# ESP12_RGBW_00.net
KiCad netlist of a schematic drawn in Altium Designer
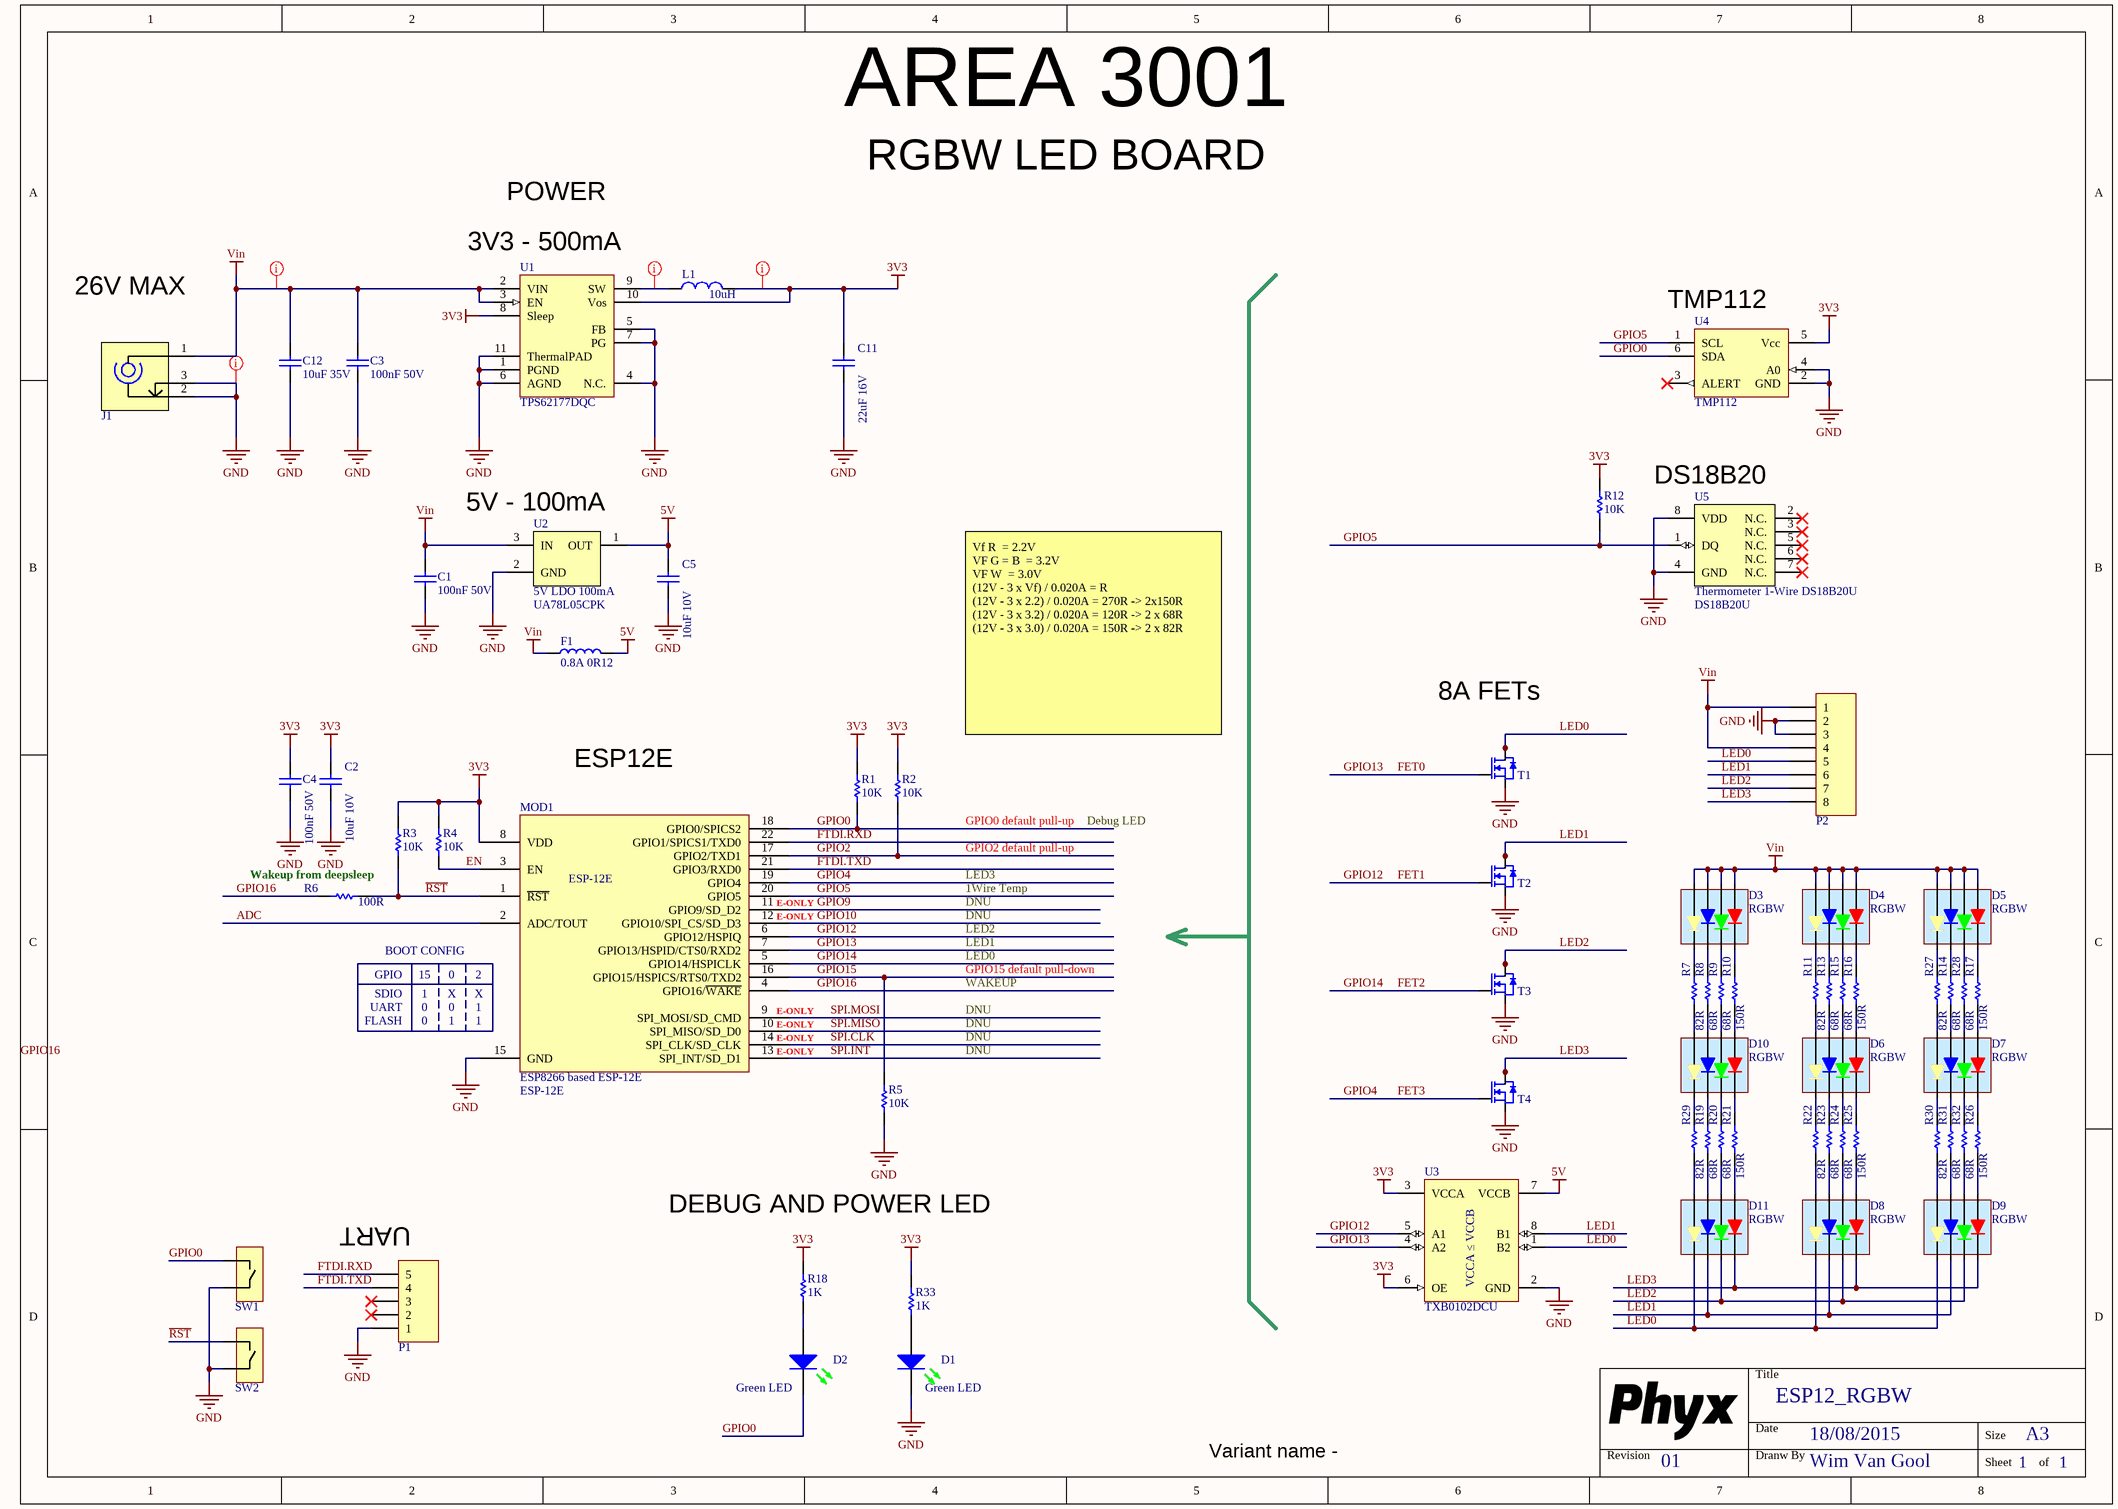
[diagram p0: ESP12_RGBW_00.SchDoc]

(export (version "E")
  (design (tool "Eeschema 10.0.6"))
  (components
    (comp (ref "C1")
      (value "100nF 50V")
      (footprint "C0603_N")
      (description "Capacitor Ceramic")
      (fields (field (name "Comment") "CAP_CERAMIC"))
      (libsource (lib "Phyx_Components") (part "CAP_CERAMIC"))
    )
    (comp (ref "C2")
      (value "10uF 10V")
      (footprint "C1206_N")
      (description "Capacitor Ceramic")
      (fields (field (name "Comment") "CAP_CERAMIC"))
      (libsource (lib "Phyx_Components") (part "CAP_CERAMIC"))
    )
    (comp (ref "C3")
      (value "100nF 50V")
      (footprint "C0603_N")
      (description "Capacitor Ceramic")
      (fields (field (name "Comment") "CAP_CERAMIC"))
      (libsource (lib "Phyx_Components") (part "CAP_CERAMIC"))
    )
    (comp (ref "C4")
      (value "100nF 50V")
      (footprint "C0603_N")
      (description "Capacitor Ceramic")
      (fields (field (name "Comment") "CAP_CERAMIC"))
      (libsource (lib "Phyx_Components") (part "CAP_CERAMIC"))
    )
    (comp (ref "C5")
      (value "10uF 10V")
      (footprint "C1206_N")
      (description "Capacitor Ceramic")
      (fields (field (name "Comment") "CAP_CERAMIC"))
      (libsource (lib "Phyx_Components") (part "CAP_CERAMIC"))
    )
    (comp (ref "C11")
      (value "22uF 16V")
      (footprint "C1206_N")
      (description "Capacitor Ceramic")
      (fields (field (name "Comment") "CAP_CERAMIC"))
      (libsource (lib "Phyx_Components") (part "CAP_CERAMIC"))
    )
    (comp (ref "C12")
      (value "10uF 35V")
      (footprint "C1206_N")
      (description "Capacitor Ceramic")
      (fields (field (name "Comment") "CAP_CERAMIC"))
      (libsource (lib "Phyx_Components") (part "CAP_CERAMIC"))
    )
    (comp (ref "D1")
      (value "Green LED")
      (footprint "LED_0805_GR")
      (description "=Description")
      (libsource (lib "Phyx_Components") (part "LED_GREEN"))
    )
    (comp (ref "D2")
      (value "Green LED")
      (footprint "LED_0805_GR")
      (description "=Description")
      (libsource (lib "Phyx_Components") (part "LED_GREEN"))
    )
    (comp (ref "D3")
      (value "RGBW")
      (footprint "LED_5050_RGBW_PLCC8")
      (description "=Description")
      (fields (field (name "Comment") "5050 RGBW LED"))
      (libsource (lib "Phyx_Components") (part "LED_RGBW"))
    )
    (comp (ref "D4")
      (value "RGBW")
      (footprint "LED_5050_RGBW_PLCC8")
      (description "=Description")
      (fields (field (name "Comment") "5050 RGBW LED"))
      (libsource (lib "Phyx_Components") (part "LED_RGBW"))
    )
    (comp (ref "D5")
      (value "RGBW")
      (footprint "LED_5050_RGBW_PLCC8")
      (description "=Description")
      (fields (field (name "Comment") "5050 RGBW LED"))
      (libsource (lib "Phyx_Components") (part "LED_RGBW"))
    )
    (comp (ref "D6")
      (value "RGBW")
      (footprint "LED_5050_RGBW_PLCC8")
      (description "=Description")
      (fields (field (name "Comment") "5050 RGBW LED"))
      (libsource (lib "Phyx_Components") (part "LED_RGBW"))
    )
    (comp (ref "D7")
      (value "RGBW")
      (footprint "LED_5050_RGBW_PLCC8")
      (description "=Description")
      (fields (field (name "Comment") "5050 RGBW LED"))
      (libsource (lib "Phyx_Components") (part "LED_RGBW"))
    )
    (comp (ref "D8")
      (value "RGBW")
      (footprint "LED_5050_RGBW_PLCC8")
      (description "=Description")
      (fields (field (name "Comment") "5050 RGBW LED"))
      (libsource (lib "Phyx_Components") (part "LED_RGBW"))
    )
    (comp (ref "D9")
      (value "RGBW")
      (footprint "LED_5050_RGBW_PLCC8")
      (description "=Description")
      (fields (field (name "Comment") "5050 RGBW LED"))
      (libsource (lib "Phyx_Components") (part "LED_RGBW"))
    )
    (comp (ref "D10")
      (value "RGBW")
      (footprint "LED_5050_RGBW_PLCC8")
      (description "=Description")
      (fields (field (name "Comment") "5050 RGBW LED"))
      (libsource (lib "Phyx_Components") (part "LED_RGBW"))
    )
    (comp (ref "D11")
      (value "RGBW")
      (footprint "LED_5050_RGBW_PLCC8")
      (description "=Description")
      (fields (field (name "Comment") "5050 RGBW LED"))
      (libsource (lib "Phyx_Components") (part "LED_RGBW"))
    )
    (comp (ref "F1")
      (value "0.8A 0R12")
      (footprint "L0805")
      (fields (field (name "Comment") "FERRITE"))
      (libsource (lib "Phyx_Components") (part "FERRITE"))
    )
    (comp (ref "J1")
      (value "Socket RA 4.75 with 1.75 barrel")
      (footprint "694105309102")
      (description "Socket RA 5.5  with 2.1 barrel")
      (libsource (lib "Phyx_Components") (part "Cliff_DC10"))
    )
    (comp (ref "L1")
      (value "10uH")
      (footprint "BRNS_SDR0503")
      (fields (field (name "Comment") "SDR0503-100ML"))
      (libsource (lib "Phyx_Components") (part "INDUCTOR"))
    )
    (comp (ref "MOD1")
      (value "ESP8266 based ESP-12E")
      (footprint "ESP-12E")
      (description "=Description")
      (fields (field (name "ALTIUM_VALUE") "ESP-12E"))
      (libsource (lib "Phyx_Components") (part "ESP-12E"))
    )
    (comp (ref "P1")
      (value "Header 5")
      (footprint "HDR1X5")
      (description "Pin Header 2.54mm 5way")
      (libsource (lib "Phyx_Components") (part "Header 5"))
    )
    (comp (ref "P2")
      (value "8 Terminal Socket RA 3,5mm")
      (footprint "WE_691322110008")
      (libsource (lib "Phyx_Components") (part "Header 8"))
    )
    (comp (ref "R1")
      (value "10K")
      (footprint "R0603_N")
      (fields (field (name "Comment") "RESISTOR"))
      (libsource (lib "Phyx_Components") (part "RESISTOR"))
    )
    (comp (ref "R2")
      (value "10K")
      (footprint "R0603_N")
      (fields (field (name "Comment") "RESISTOR"))
      (libsource (lib "Phyx_Components") (part "RESISTOR"))
    )
    (comp (ref "R3")
      (value "10K")
      (footprint "R0603_N")
      (fields (field (name "Comment") "RESISTOR"))
      (libsource (lib "Phyx_Components") (part "RESISTOR"))
    )
    (comp (ref "R4")
      (value "10K")
      (footprint "R0603_N")
      (fields (field (name "Comment") "RESISTOR"))
      (libsource (lib "Phyx_Components") (part "RESISTOR"))
    )
    (comp (ref "R5")
      (value "10K")
      (footprint "R0603_N")
      (fields (field (name "Comment") "RESISTOR"))
      (libsource (lib "Phyx_Components") (part "RESISTOR"))
    )
    (comp (ref "R6")
      (value "100R")
      (footprint "R0603_N")
      (fields (field (name "Comment") "RESISTOR"))
      (libsource (lib "Phyx_Components") (part "RESISTOR"))
    )
    (comp (ref "R7")
      (value "82R")
      (footprint "R0603_N")
      (description "RES # 82R 0603")
      (fields (field (name "Comment") "RESISTOR"))
      (libsource (lib "Phyx_Components") (part "RESISTOR"))
    )
    (comp (ref "R8")
      (value "68R")
      (footprint "R0603_N")
      (fields (field (name "Comment") "RESISTOR"))
      (libsource (lib "Phyx_Components") (part "RESISTOR"))
    )
    (comp (ref "R9")
      (value "68R")
      (footprint "R0603_N")
      (fields (field (name "Comment") "RESISTOR"))
      (libsource (lib "Phyx_Components") (part "RESISTOR"))
    )
    (comp (ref "R10")
      (value "150R")
      (footprint "R0603_N")
      (description "RES # 150R 0603")
      (fields (field (name "Comment") "RESISTOR"))
      (libsource (lib "Phyx_Components") (part "RESISTOR"))
    )
    (comp (ref "R11")
      (value "82R")
      (footprint "R0603_N")
      (description "RES # 82R 0603")
      (fields (field (name "Comment") "RESISTOR"))
      (libsource (lib "Phyx_Components") (part "RESISTOR"))
    )
    (comp (ref "R12")
      (value "10K")
      (footprint "R0603_N")
      (fields (field (name "Comment") "RESISTOR"))
      (libsource (lib "Phyx_Components") (part "RESISTOR"))
    )
    (comp (ref "R13")
      (value "68R")
      (footprint "R0603_N")
      (fields (field (name "Comment") "RESISTOR"))
      (libsource (lib "Phyx_Components") (part "RESISTOR"))
    )
    (comp (ref "R14")
      (value "68R")
      (footprint "R0603_N")
      (fields (field (name "Comment") "RESISTOR"))
      (libsource (lib "Phyx_Components") (part "RESISTOR"))
    )
    (comp (ref "R15")
      (value "68R")
      (footprint "R0603_N")
      (fields (field (name "Comment") "RESISTOR"))
      (libsource (lib "Phyx_Components") (part "RESISTOR"))
    )
    (comp (ref "R16")
      (value "150R")
      (footprint "R0603_N")
      (description "RES # 150R 0603")
      (fields (field (name "Comment") "RESISTOR"))
      (libsource (lib "Phyx_Components") (part "RESISTOR"))
    )
    (comp (ref "R17")
      (value "150R")
      (footprint "R0603_N")
      (description "RES # 150R 0603")
      (fields (field (name "Comment") "RESISTOR"))
      (libsource (lib "Phyx_Components") (part "RESISTOR"))
    )
    (comp (ref "R18")
      (value "1K")
      (footprint "R0603_N")
      (fields (field (name "Comment") "RESISTOR"))
      (libsource (lib "Phyx_Components") (part "RESISTOR"))
    )
    (comp (ref "R19")
      (value "68R")
      (footprint "R0603_N")
      (fields (field (name "Comment") "RESISTOR"))
      (libsource (lib "Phyx_Components") (part "RESISTOR"))
    )
    (comp (ref "R20")
      (value "68R")
      (footprint "R0603_N")
      (fields (field (name "Comment") "RESISTOR"))
      (libsource (lib "Phyx_Components") (part "RESISTOR"))
    )
    (comp (ref "R21")
      (value "150R")
      (footprint "R0603_N")
      (description "RES # 150R 0603")
      (fields (field (name "Comment") "RESISTOR"))
      (libsource (lib "Phyx_Components") (part "RESISTOR"))
    )
    (comp (ref "R22")
      (value "82R")
      (footprint "R0603_N")
      (description "RES # 82R 0603")
      (fields (field (name "Comment") "RESISTOR"))
      (libsource (lib "Phyx_Components") (part "RESISTOR"))
    )
    (comp (ref "R23")
      (value "68R")
      (footprint "R0603_N")
      (fields (field (name "Comment") "RESISTOR"))
      (libsource (lib "Phyx_Components") (part "RESISTOR"))
    )
    (comp (ref "R24")
      (value "68R")
      (footprint "R0603_N")
      (fields (field (name "Comment") "RESISTOR"))
      (libsource (lib "Phyx_Components") (part "RESISTOR"))
    )
    (comp (ref "R25")
      (value "150R")
      (footprint "R0603_N")
      (description "RES # 150R 0603")
      (fields (field (name "Comment") "RESISTOR"))
      (libsource (lib "Phyx_Components") (part "RESISTOR"))
    )
    (comp (ref "R26")
      (value "150R")
      (footprint "R0603_N")
      (description "RES # 150R 0603")
      (fields (field (name "Comment") "RESISTOR"))
      (libsource (lib "Phyx_Components") (part "RESISTOR"))
    )
    (comp (ref "R27")
      (value "82R")
      (footprint "R0603_N")
      (description "RES # 82R 0603")
      (fields (field (name "Comment") "RESISTOR"))
      (libsource (lib "Phyx_Components") (part "RESISTOR"))
    )
    (comp (ref "R28")
      (value "68R")
      (footprint "R0603_N")
      (fields (field (name "Comment") "RESISTOR"))
      (libsource (lib "Phyx_Components") (part "RESISTOR"))
    )
    (comp (ref "R29")
      (value "82R")
      (footprint "R0603_N")
      (description "RES # 82R 0603")
      (fields (field (name "Comment") "RESISTOR"))
      (libsource (lib "Phyx_Components") (part "RESISTOR"))
    )
    (comp (ref "R30")
      (value "82R")
      (footprint "R0603_N")
      (description "RES # 82R 0603")
      (fields (field (name "Comment") "RESISTOR"))
      (libsource (lib "Phyx_Components") (part "RESISTOR"))
    )
    (comp (ref "R31")
      (value "68R")
      (footprint "R0603_N")
      (fields (field (name "Comment") "RESISTOR"))
      (libsource (lib "Phyx_Components") (part "RESISTOR"))
    )
    (comp (ref "R32")
      (value "68R")
      (footprint "R0603_N")
      (fields (field (name "Comment") "RESISTOR"))
      (libsource (lib "Phyx_Components") (part "RESISTOR"))
    )
    (comp (ref "R33")
      (value "1K")
      (footprint "R0603_N")
      (fields (field (name "Comment") "RESISTOR"))
      (libsource (lib "Phyx_Components") (part "RESISTOR"))
    )
    (comp (ref "SW1")
      (value "LP SMD tact sw WS-TASV")
      (footprint "WE_434153017835")
      (description "SW # TACT mini 3.5x2.9 mm SMD J-Bend WS-TASV")
      (libsource (lib "Phyx_Components") (part "SW_TACT"))
    )
    (comp (ref "SW2")
      (value "LP SMD tact sw WS-TASV")
      (footprint "WE_434153017835")
      (description "SW # TACT mini 3.5x2.9 mm SMD J-Bend WS-TASV")
      (libsource (lib "Phyx_Components") (part "SW_TACT"))
    )
    (comp (ref "T1")
      (value "8A N-Ch MOSFET Vgs 1.9")
      (footprint "SOT23-6")
      (libsource (lib "Phyx_Components") (part "N_MOSFET_DDGSDD"))
    )
    (comp (ref "T2")
      (value "8A N-Ch MOSFET Vgs 1.9")
      (footprint "SOT23-6")
      (libsource (lib "Phyx_Components") (part "N_MOSFET_DDGSDD"))
    )
    (comp (ref "T3")
      (value "8A N-Ch MOSFET Vgs 1.9")
      (footprint "SOT23-6")
      (libsource (lib "Phyx_Components") (part "N_MOSFET_DDGSDD"))
    )
    (comp (ref "T4")
      (value "8A N-Ch MOSFET Vgs 1.9")
      (footprint "SOT23-6")
      (libsource (lib "Phyx_Components") (part "N_MOSFET_DDGSDD"))
    )
    (comp (ref "U1")
      (value "TPS62177DQC")
      (footprint "TI_DQC_WSON10")
      (description "=Description")
      (fields (field (name "Comment") "Fixed 3.3V Buck 0.5A"))
      (libsource (lib "Phyx_Components") (part "TPS62177"))
    )
    (comp (ref "U2")
      (value "5V LDO 100mA")
      (footprint "TI_PK")
      (description "LDO 5V 100mA")
      (fields (field (name "ALTIUM_VALUE") "UA78L05CPK"))
      (libsource (lib "Phyx_Components") (part "UA78L05CPK"))
    )
    (comp (ref "U3")
      (value "TXB0102DCU")
      (footprint "TI_DCU_R-PDSO-G8")
      (description "=Description")
      (fields (field (name "Comment") "2-bit Bi Level translator, 15kV ESD"))
      (libsource (lib "Phyx_Components") (part "TXB0102DCU"))
    )
    (comp (ref "U4")
      (value "TMP112")
      (footprint "TI_DRL_R-PDSO-N6")
      (description "=Description")
      (fields (field (name "Comment") "I2C Temp sensor High Accuracy"))
      (libsource (lib "Phyx_Components") (part "TMP1x2"))
    )
    (comp (ref "U5")
      (value "Thermometer 1-Wire DS18B20U")
      (footprint "MAX_uSOP8")
      (description "=Description")
      (fields (field (name "ALTIUM_VALUE") "DS18B20U"))
      (libsource (lib "Phyx_Components") (part "DS18B20U"))
    )
  )
  (nets
    (net (code "1") (name "/ADC") (class "Default")
      (node (ref "MOD1") (pin "2") (pinfunction "ADC/TOUT_2") (pintype "passive"))
    )
    (net (code "2") (name "/EN") (class "Default")
      (node (ref "MOD1") (pin "3") (pinfunction "EN_3") (pintype "passive"))
      (node (ref "R4") (pin "2") (pinfunction "2_2") (pintype "passive"))
    )
    (net (code "3") (name "/FET0") (class "Default")
      (node (ref "MOD1") (pin "7") (pinfunction "GPIO13/HSPID/CTS0/RXD2_7") (pintype "passive"))
      (node (ref "T1") (pin "3") (pinfunction "G_3") (pintype "passive"))
      (node (ref "U3") (pin "4") (pinfunction "A2_4") (pintype "bidirectional"))
    )
    (net (code "4") (name "/FET1") (class "Default")
      (node (ref "MOD1") (pin "6") (pinfunction "GPIO12/HSPIQ_6") (pintype "passive"))
      (node (ref "T2") (pin "3") (pinfunction "G_3") (pintype "passive"))
      (node (ref "U3") (pin "5") (pinfunction "A1_5") (pintype "bidirectional"))
    )
    (net (code "5") (name "/FET2") (class "Default")
      (node (ref "MOD1") (pin "5") (pinfunction "GPIO14/HSPICLK_5") (pintype "passive"))
      (node (ref "T3") (pin "3") (pinfunction "G_3") (pintype "passive"))
    )
    (net (code "6") (name "/FET3") (class "Default")
      (node (ref "MOD1") (pin "19") (pinfunction "GPIO4_19") (pintype "passive"))
      (node (ref "T4") (pin "3") (pinfunction "G_3") (pintype "passive"))
    )
    (net (code "7") (name "/FTDI.RXD") (class "Default")
      (node (ref "MOD1") (pin "22") (pinfunction "GPIO1/SPICS1/TXD0_22") (pintype "passive"))
      (node (ref "P1") (pin "5") (pinfunction "5_5") (pintype "passive"))
    )
    (net (code "8") (name "/FTDI.TXD") (class "Default")
      (node (ref "MOD1") (pin "21") (pinfunction "GPIO3/RXD0_21") (pintype "passive"))
      (node (ref "P1") (pin "4") (pinfunction "4_4") (pintype "passive"))
    )
    (net (code "9") (name "/GPIO0") (class "Default")
      (node (ref "D2") (pin "2") (pinfunction "K_2") (pintype "passive"))
      (node (ref "MOD1") (pin "18") (pinfunction "GPIO0/SPICS2_18") (pintype "passive"))
      (node (ref "R1") (pin "2") (pinfunction "2_2") (pintype "passive"))
      (node (ref "SW1") (pin "1") (pinfunction "1_1") (pintype "passive"))
      (node (ref "U4") (pin "6") (pinfunction "SDA_6") (pintype "open_collector"))
    )
    (net (code "10") (name "/GPIO2") (class "Default")
      (node (ref "MOD1") (pin "17") (pinfunction "GPIO2/TXD1_17") (pintype "passive"))
      (node (ref "R2") (pin "2") (pinfunction "2_2") (pintype "passive"))
    )
    (net (code "11") (name "/GPIO5") (class "Default")
      (node (ref "MOD1") (pin "20") (pinfunction "GPIO5_20") (pintype "passive"))
      (node (ref "R12") (pin "2") (pinfunction "2_2") (pintype "passive"))
      (node (ref "U4") (pin "1") (pinfunction "SCL_1") (pintype "open_collector"))
      (node (ref "U5") (pin "1") (pinfunction "DQ_1") (pintype "bidirectional"))
    )
    (net (code "12") (name "/GPIO9") (class "Default")
      (node (ref "MOD1") (pin "11") (pinfunction "GPIO9/SD_D2_11") (pintype "passive"))
    )
    (net (code "13") (name "/GPIO10") (class "Default")
      (node (ref "MOD1") (pin "12") (pinfunction "GPIO10/SPI_CS/SD_D3_12") (pintype "passive"))
    )
    (net (code "14") (name "/GPIO15") (class "Default")
      (node (ref "MOD1") (pin "16") (pinfunction "GPIO15/HSPICS/RTS0/TXD2_16") (pintype "passive"))
      (node (ref "R5") (pin "1") (pinfunction "1_1") (pintype "passive"))
    )
    (net (code "15") (name "/GPIO16") (class "Default")
      (node (ref "MOD1") (pin "4") (pinfunction "GPIO16/~{WAKE}_4") (pintype "passive"))
      (node (ref "R6") (pin "2") (pinfunction "2_2") (pintype "passive"))
    )
    (net (code "16") (name "/LED0") (class "Default")
      (node (ref "D11") (pin "8") (pinfunction "WC_8") (pintype "passive"))
      (node (ref "D8") (pin "8") (pinfunction "WC_8") (pintype "passive"))
      (node (ref "D9") (pin "8") (pinfunction "WC_8") (pintype "passive"))
      (node (ref "P2") (pin "5") (pinfunction "5_5") (pintype "passive"))
      (node (ref "T1") (pin "1") (pinfunction "D_1") (pintype "passive"))
      (node (ref "T1") (pin "2") (pinfunction "D_2") (pintype "passive"))
      (node (ref "T1") (pin "5") (pinfunction "D_5") (pintype "passive"))
      (node (ref "T1") (pin "6") (pinfunction "D_6") (pintype "passive"))
      (node (ref "U3") (pin "1") (pinfunction "B2_1") (pintype "bidirectional"))
    )
    (net (code "17") (name "/LED1") (class "Default")
      (node (ref "D11") (pin "6") (pinfunction "BC_6") (pintype "passive"))
      (node (ref "D8") (pin "6") (pinfunction "BC_6") (pintype "passive"))
      (node (ref "D9") (pin "6") (pinfunction "BC_6") (pintype "passive"))
      (node (ref "P2") (pin "6") (pinfunction "6_6") (pintype "passive"))
      (node (ref "T2") (pin "1") (pinfunction "D_1") (pintype "passive"))
      (node (ref "T2") (pin "2") (pinfunction "D_2") (pintype "passive"))
      (node (ref "T2") (pin "5") (pinfunction "D_5") (pintype "passive"))
      (node (ref "T2") (pin "6") (pinfunction "D_6") (pintype "passive"))
      (node (ref "U3") (pin "8") (pinfunction "B1_8") (pintype "bidirectional"))
    )
    (net (code "18") (name "/LED2") (class "Default")
      (node (ref "D11") (pin "4") (pinfunction "GC_4") (pintype "passive"))
      (node (ref "D8") (pin "4") (pinfunction "GC_4") (pintype "passive"))
      (node (ref "D9") (pin "4") (pinfunction "GC_4") (pintype "passive"))
      (node (ref "P2") (pin "7") (pinfunction "7_7") (pintype "passive"))
      (node (ref "T3") (pin "1") (pinfunction "D_1") (pintype "passive"))
      (node (ref "T3") (pin "2") (pinfunction "D_2") (pintype "passive"))
      (node (ref "T3") (pin "5") (pinfunction "D_5") (pintype "passive"))
      (node (ref "T3") (pin "6") (pinfunction "D_6") (pintype "passive"))
    )
    (net (code "19") (name "/LED3") (class "Default")
      (node (ref "D11") (pin "2") (pinfunction "RC_2") (pintype "passive"))
      (node (ref "D8") (pin "2") (pinfunction "RC_2") (pintype "passive"))
      (node (ref "D9") (pin "2") (pinfunction "RC_2") (pintype "passive"))
      (node (ref "P2") (pin "8") (pinfunction "8_8") (pintype "passive"))
      (node (ref "T4") (pin "1") (pinfunction "D_1") (pintype "passive"))
      (node (ref "T4") (pin "2") (pinfunction "D_2") (pintype "passive"))
      (node (ref "T4") (pin "5") (pinfunction "D_5") (pintype "passive"))
      (node (ref "T4") (pin "6") (pinfunction "D_6") (pintype "passive"))
    )
    (net (code "20") (name "/SPI.CLK") (class "Default")
      (node (ref "MOD1") (pin "14") (pinfunction "SPI_CLK/SD_CLK_14") (pintype "passive"))
    )
    (net (code "21") (name "/SPI.INT") (class "Default")
      (node (ref "MOD1") (pin "13") (pinfunction "SPI_INT/SD_D1_13") (pintype "passive"))
    )
    (net (code "22") (name "/SPI.MISO") (class "Default")
      (node (ref "MOD1") (pin "10") (pinfunction "SPI_MISO/SD_D0_10") (pintype "passive"))
    )
    (net (code "23") (name "/SPI.MOSI") (class "Default")
      (node (ref "MOD1") (pin "9") (pinfunction "SPI_MOSI/SD_CMD_9") (pintype "passive"))
    )
    (net (code "24") (name "/~{RST}") (class "Default")
      (node (ref "MOD1") (pin "1") (pinfunction "~{RST}_1") (pintype "passive"))
      (node (ref "R3") (pin "2") (pinfunction "2_2") (pintype "passive"))
      (node (ref "R6") (pin "1") (pinfunction "1_1") (pintype "passive"))
      (node (ref "SW2") (pin "1") (pinfunction "1_1") (pintype "passive"))
    )
    (net (code "25") (name "3V3") (class "Default")
      (node (ref "C11") (pin "1") (pinfunction "1_1") (pintype "passive"))
      (node (ref "C2") (pin "1") (pinfunction "1_1") (pintype "passive"))
      (node (ref "C4") (pin "1") (pinfunction "1_1") (pintype "passive"))
      (node (ref "L1") (pin "2") (pinfunction "2_2") (pintype "passive"))
      (node (ref "MOD1") (pin "8") (pinfunction "VDD_8") (pintype "passive"))
      (node (ref "R1") (pin "1") (pinfunction "1_1") (pintype "passive"))
      (node (ref "R12") (pin "1") (pinfunction "1_1") (pintype "passive"))
      (node (ref "R18") (pin "1") (pinfunction "1_1") (pintype "passive"))
      (node (ref "R2") (pin "1") (pinfunction "1_1") (pintype "passive"))
      (node (ref "R3") (pin "1") (pinfunction "1_1") (pintype "passive"))
      (node (ref "R33") (pin "1") (pinfunction "1_1") (pintype "passive"))
      (node (ref "R4") (pin "1") (pinfunction "1_1") (pintype "passive"))
      (node (ref "U1") (pin "10") (pinfunction "Vos_10") (pintype "passive"))
      (node (ref "U1") (pin "8") (pinfunction "Sleep_8") (pintype "passive"))
      (node (ref "U3") (pin "3") (pinfunction "VCCA_3") (pintype "power_in"))
      (node (ref "U3") (pin "6") (pinfunction "OE_6") (pintype "input"))
      (node (ref "U4") (pin "5") (pinfunction "Vcc_5") (pintype "power_in"))
    )
    (net (code "26") (name "5V") (class "Default")
      (node (ref "C5") (pin "1") (pinfunction "1_1") (pintype "passive"))
      (node (ref "F1") (pin "2") (pinfunction "2_2") (pintype "passive"))
      (node (ref "U2") (pin "1") (pinfunction "OUT_1") (pintype "passive"))
      (node (ref "U3") (pin "7") (pinfunction "VCCB_7") (pintype "power_in"))
    )
    (net (code "27") (name "GND") (class "Default")
      (node (ref "C1") (pin "2") (pinfunction "2_2") (pintype "passive"))
      (node (ref "C11") (pin "2") (pinfunction "2_2") (pintype "passive"))
      (node (ref "C12") (pin "2") (pinfunction "2_2") (pintype "passive"))
      (node (ref "C2") (pin "2") (pinfunction "2_2") (pintype "passive"))
      (node (ref "C3") (pin "2") (pinfunction "2_2") (pintype "passive"))
      (node (ref "C4") (pin "2") (pinfunction "2_2") (pintype "passive"))
      (node (ref "C5") (pin "2") (pinfunction "2_2") (pintype "passive"))
      (node (ref "D1") (pin "2") (pinfunction "K_2") (pintype "passive"))
      (node (ref "J1") (pin "2") (pinfunction "2_2") (pintype "passive"))
      (node (ref "J1") (pin "3") (pinfunction "3_3") (pintype "passive"))
      (node (ref "MOD1") (pin "15") (pinfunction "GND_15") (pintype "passive"))
      (node (ref "P1") (pin "1") (pinfunction "1_1") (pintype "passive"))
      (node (ref "P2") (pin "2") (pinfunction "2_2") (pintype "passive"))
      (node (ref "P2") (pin "3") (pinfunction "3_3") (pintype "passive"))
      (node (ref "R5") (pin "2") (pinfunction "2_2") (pintype "passive"))
      (node (ref "SW1") (pin "2") (pinfunction "2_2") (pintype "passive"))
      (node (ref "SW2") (pin "2") (pinfunction "2_2") (pintype "passive"))
      (node (ref "T1") (pin "4") (pinfunction "S_4") (pintype "passive"))
      (node (ref "T2") (pin "4") (pinfunction "S_4") (pintype "passive"))
      (node (ref "T3") (pin "4") (pinfunction "S_4") (pintype "passive"))
      (node (ref "T4") (pin "4") (pinfunction "S_4") (pintype "passive"))
      (node (ref "U1") (pin "1") (pinfunction "PGND_1") (pintype "power_in"))
      (node (ref "U1") (pin "11") (pinfunction "ThermalPAD_11") (pintype "power_in"))
      (node (ref "U1") (pin "4") (pinfunction "N.C._4") (pintype "passive"))
      (node (ref "U1") (pin "5") (pinfunction "FB_5") (pintype "passive"))
      (node (ref "U1") (pin "6") (pinfunction "AGND_6") (pintype "power_in"))
      (node (ref "U1") (pin "7") (pinfunction "PG_7") (pintype "passive"))
      (node (ref "U2") (pin "2") (pinfunction "GND_2") (pintype "passive"))
      (node (ref "U3") (pin "2") (pinfunction "GND_2") (pintype "power_in"))
      (node (ref "U4") (pin "2") (pinfunction "GND_2") (pintype "power_in"))
      (node (ref "U4") (pin "4") (pinfunction "A0_4") (pintype "input"))
      (node (ref "U5") (pin "4") (pinfunction "GND_4") (pintype "power_in"))
      (node (ref "U5") (pin "8") (pinfunction "VDD_8") (pintype "power_in"))
    )
    (net (code "28") (name "Net-(D1-A)") (class "Default")
      (node (ref "D1") (pin "1") (pinfunction "A_1") (pintype "passive"))
      (node (ref "R33") (pin "2") (pinfunction "2_2") (pintype "passive"))
    )
    (net (code "29") (name "Net-(D2-A)") (class "Default")
      (node (ref "D2") (pin "1") (pinfunction "A_1") (pintype "passive"))
      (node (ref "R18") (pin "2") (pinfunction "2_2") (pintype "passive"))
    )
    (net (code "30") (name "Net-(D3-BC)") (class "Default")
      (node (ref "D3") (pin "6") (pinfunction "BC_6") (pintype "passive"))
      (node (ref "R8") (pin "1") (pinfunction "1_1") (pintype "passive"))
    )
    (net (code "31") (name "Net-(D3-GC)") (class "Default")
      (node (ref "D3") (pin "4") (pinfunction "GC_4") (pintype "passive"))
      (node (ref "R9") (pin "1") (pinfunction "1_1") (pintype "passive"))
    )
    (net (code "32") (name "Net-(D3-RC)") (class "Default")
      (node (ref "D3") (pin "2") (pinfunction "RC_2") (pintype "passive"))
      (node (ref "R10") (pin "1") (pinfunction "1_1") (pintype "passive"))
    )
    (net (code "33") (name "Net-(D3-WC)") (class "Default")
      (node (ref "D3") (pin "8") (pinfunction "WC_8") (pintype "passive"))
      (node (ref "R7") (pin "1") (pinfunction "1_1") (pintype "passive"))
    )
    (net (code "34") (name "Net-(D4-BC)") (class "Default")
      (node (ref "D4") (pin "6") (pinfunction "BC_6") (pintype "passive"))
      (node (ref "R13") (pin "1") (pinfunction "1_1") (pintype "passive"))
    )
    (net (code "35") (name "Net-(D4-GC)") (class "Default")
      (node (ref "D4") (pin "4") (pinfunction "GC_4") (pintype "passive"))
      (node (ref "R15") (pin "1") (pinfunction "1_1") (pintype "passive"))
    )
    (net (code "36") (name "Net-(D4-RC)") (class "Default")
      (node (ref "D4") (pin "2") (pinfunction "RC_2") (pintype "passive"))
      (node (ref "R16") (pin "1") (pinfunction "1_1") (pintype "passive"))
    )
    (net (code "37") (name "Net-(D4-WC)") (class "Default")
      (node (ref "D4") (pin "8") (pinfunction "WC_8") (pintype "passive"))
      (node (ref "R11") (pin "1") (pinfunction "1_1") (pintype "passive"))
    )
    (net (code "38") (name "Net-(D5-BC)") (class "Default")
      (node (ref "D5") (pin "6") (pinfunction "BC_6") (pintype "passive"))
      (node (ref "R14") (pin "1") (pinfunction "1_1") (pintype "passive"))
    )
    (net (code "39") (name "Net-(D5-GC)") (class "Default")
      (node (ref "D5") (pin "4") (pinfunction "GC_4") (pintype "passive"))
      (node (ref "R28") (pin "1") (pinfunction "1_1") (pintype "passive"))
    )
    (net (code "40") (name "Net-(D5-RC)") (class "Default")
      (node (ref "D5") (pin "2") (pinfunction "RC_2") (pintype "passive"))
      (node (ref "R17") (pin "1") (pinfunction "1_1") (pintype "passive"))
    )
    (net (code "41") (name "Net-(D5-WC)") (class "Default")
      (node (ref "D5") (pin "8") (pinfunction "WC_8") (pintype "passive"))
      (node (ref "R27") (pin "1") (pinfunction "1_1") (pintype "passive"))
    )
    (net (code "42") (name "Net-(D6-BA)") (class "Default")
      (node (ref "D6") (pin "5") (pinfunction "BA_5") (pintype "passive"))
      (node (ref "R13") (pin "2") (pinfunction "2_2") (pintype "passive"))
    )
    (net (code "43") (name "Net-(D6-BC)") (class "Default")
      (node (ref "D6") (pin "6") (pinfunction "BC_6") (pintype "passive"))
      (node (ref "R23") (pin "1") (pinfunction "1_1") (pintype "passive"))
    )
    (net (code "44") (name "Net-(D6-GA)") (class "Default")
      (node (ref "D6") (pin "3") (pinfunction "GA_3") (pintype "passive"))
      (node (ref "R15") (pin "2") (pinfunction "2_2") (pintype "passive"))
    )
    (net (code "45") (name "Net-(D6-GC)") (class "Default")
      (node (ref "D6") (pin "4") (pinfunction "GC_4") (pintype "passive"))
      (node (ref "R24") (pin "1") (pinfunction "1_1") (pintype "passive"))
    )
    (net (code "46") (name "Net-(D6-RA)") (class "Default")
      (node (ref "D6") (pin "1") (pinfunction "RA_1") (pintype "passive"))
      (node (ref "R16") (pin "2") (pinfunction "2_2") (pintype "passive"))
    )
    (net (code "47") (name "Net-(D6-RC)") (class "Default")
      (node (ref "D6") (pin "2") (pinfunction "RC_2") (pintype "passive"))
      (node (ref "R25") (pin "1") (pinfunction "1_1") (pintype "passive"))
    )
    (net (code "48") (name "Net-(D6-WA)") (class "Default")
      (node (ref "D6") (pin "7") (pinfunction "WA_7") (pintype "passive"))
      (node (ref "R11") (pin "2") (pinfunction "2_2") (pintype "passive"))
    )
    (net (code "49") (name "Net-(D6-WC)") (class "Default")
      (node (ref "D6") (pin "8") (pinfunction "WC_8") (pintype "passive"))
      (node (ref "R22") (pin "1") (pinfunction "1_1") (pintype "passive"))
    )
    (net (code "50") (name "Net-(D7-BA)") (class "Default")
      (node (ref "D7") (pin "5") (pinfunction "BA_5") (pintype "passive"))
      (node (ref "R14") (pin "2") (pinfunction "2_2") (pintype "passive"))
    )
    (net (code "51") (name "Net-(D7-BC)") (class "Default")
      (node (ref "D7") (pin "6") (pinfunction "BC_6") (pintype "passive"))
      (node (ref "R31") (pin "1") (pinfunction "1_1") (pintype "passive"))
    )
    (net (code "52") (name "Net-(D7-GA)") (class "Default")
      (node (ref "D7") (pin "3") (pinfunction "GA_3") (pintype "passive"))
      (node (ref "R28") (pin "2") (pinfunction "2_2") (pintype "passive"))
    )
    (net (code "53") (name "Net-(D7-GC)") (class "Default")
      (node (ref "D7") (pin "4") (pinfunction "GC_4") (pintype "passive"))
      (node (ref "R32") (pin "1") (pinfunction "1_1") (pintype "passive"))
    )
    (net (code "54") (name "Net-(D7-RA)") (class "Default")
      (node (ref "D7") (pin "1") (pinfunction "RA_1") (pintype "passive"))
      (node (ref "R17") (pin "2") (pinfunction "2_2") (pintype "passive"))
    )
    (net (code "55") (name "Net-(D7-RC)") (class "Default")
      (node (ref "D7") (pin "2") (pinfunction "RC_2") (pintype "passive"))
      (node (ref "R26") (pin "1") (pinfunction "1_1") (pintype "passive"))
    )
    (net (code "56") (name "Net-(D7-WA)") (class "Default")
      (node (ref "D7") (pin "7") (pinfunction "WA_7") (pintype "passive"))
      (node (ref "R27") (pin "2") (pinfunction "2_2") (pintype "passive"))
    )
    (net (code "57") (name "Net-(D7-WC)") (class "Default")
      (node (ref "D7") (pin "8") (pinfunction "WC_8") (pintype "passive"))
      (node (ref "R30") (pin "1") (pinfunction "1_1") (pintype "passive"))
    )
    (net (code "58") (name "Net-(D8-BA)") (class "Default")
      (node (ref "D8") (pin "5") (pinfunction "BA_5") (pintype "passive"))
      (node (ref "R23") (pin "2") (pinfunction "2_2") (pintype "passive"))
    )
    (net (code "59") (name "Net-(D8-GA)") (class "Default")
      (node (ref "D8") (pin "3") (pinfunction "GA_3") (pintype "passive"))
      (node (ref "R24") (pin "2") (pinfunction "2_2") (pintype "passive"))
    )
    (net (code "60") (name "Net-(D8-RA)") (class "Default")
      (node (ref "D8") (pin "1") (pinfunction "RA_1") (pintype "passive"))
      (node (ref "R25") (pin "2") (pinfunction "2_2") (pintype "passive"))
    )
    (net (code "61") (name "Net-(D8-WA)") (class "Default")
      (node (ref "D8") (pin "7") (pinfunction "WA_7") (pintype "passive"))
      (node (ref "R22") (pin "2") (pinfunction "2_2") (pintype "passive"))
    )
    (net (code "62") (name "Net-(D9-BA)") (class "Default")
      (node (ref "D9") (pin "5") (pinfunction "BA_5") (pintype "passive"))
      (node (ref "R31") (pin "2") (pinfunction "2_2") (pintype "passive"))
    )
    (net (code "63") (name "Net-(D9-GA)") (class "Default")
      (node (ref "D9") (pin "3") (pinfunction "GA_3") (pintype "passive"))
      (node (ref "R32") (pin "2") (pinfunction "2_2") (pintype "passive"))
    )
    (net (code "64") (name "Net-(D9-RA)") (class "Default")
      (node (ref "D9") (pin "1") (pinfunction "RA_1") (pintype "passive"))
      (node (ref "R26") (pin "2") (pinfunction "2_2") (pintype "passive"))
    )
    (net (code "65") (name "Net-(D9-WA)") (class "Default")
      (node (ref "D9") (pin "7") (pinfunction "WA_7") (pintype "passive"))
      (node (ref "R30") (pin "2") (pinfunction "2_2") (pintype "passive"))
    )
    (net (code "66") (name "Net-(D10-BA)") (class "Default")
      (node (ref "D10") (pin "5") (pinfunction "BA_5") (pintype "passive"))
      (node (ref "R8") (pin "2") (pinfunction "2_2") (pintype "passive"))
    )
    (net (code "67") (name "Net-(D10-BC)") (class "Default")
      (node (ref "D10") (pin "6") (pinfunction "BC_6") (pintype "passive"))
      (node (ref "R19") (pin "1") (pinfunction "1_1") (pintype "passive"))
    )
    (net (code "68") (name "Net-(D10-GA)") (class "Default")
      (node (ref "D10") (pin "3") (pinfunction "GA_3") (pintype "passive"))
      (node (ref "R9") (pin "2") (pinfunction "2_2") (pintype "passive"))
    )
    (net (code "69") (name "Net-(D10-GC)") (class "Default")
      (node (ref "D10") (pin "4") (pinfunction "GC_4") (pintype "passive"))
      (node (ref "R20") (pin "1") (pinfunction "1_1") (pintype "passive"))
    )
    (net (code "70") (name "Net-(D10-RA)") (class "Default")
      (node (ref "D10") (pin "1") (pinfunction "RA_1") (pintype "passive"))
      (node (ref "R10") (pin "2") (pinfunction "2_2") (pintype "passive"))
    )
    (net (code "71") (name "Net-(D10-RC)") (class "Default")
      (node (ref "D10") (pin "2") (pinfunction "RC_2") (pintype "passive"))
      (node (ref "R21") (pin "1") (pinfunction "1_1") (pintype "passive"))
    )
    (net (code "72") (name "Net-(D10-WA)") (class "Default")
      (node (ref "D10") (pin "7") (pinfunction "WA_7") (pintype "passive"))
      (node (ref "R7") (pin "2") (pinfunction "2_2") (pintype "passive"))
    )
    (net (code "73") (name "Net-(D10-WC)") (class "Default")
      (node (ref "D10") (pin "8") (pinfunction "WC_8") (pintype "passive"))
      (node (ref "R29") (pin "1") (pinfunction "1_1") (pintype "passive"))
    )
    (net (code "74") (name "Net-(D11-BA)") (class "Default")
      (node (ref "D11") (pin "5") (pinfunction "BA_5") (pintype "passive"))
      (node (ref "R19") (pin "2") (pinfunction "2_2") (pintype "passive"))
    )
    (net (code "75") (name "Net-(D11-GA)") (class "Default")
      (node (ref "D11") (pin "3") (pinfunction "GA_3") (pintype "passive"))
      (node (ref "R20") (pin "2") (pinfunction "2_2") (pintype "passive"))
    )
    (net (code "76") (name "Net-(D11-RA)") (class "Default")
      (node (ref "D11") (pin "1") (pinfunction "RA_1") (pintype "passive"))
      (node (ref "R21") (pin "2") (pinfunction "2_2") (pintype "passive"))
    )
    (net (code "77") (name "Net-(D11-WA)") (class "Default")
      (node (ref "D11") (pin "7") (pinfunction "WA_7") (pintype "passive"))
      (node (ref "R29") (pin "2") (pinfunction "2_2") (pintype "passive"))
    )
    (net (code "78") (name "Net-(U1-SW)") (class "Default")
      (node (ref "L1") (pin "1") (pinfunction "1_1") (pintype "passive"))
      (node (ref "U1") (pin "9") (pinfunction "SW_9") (pintype "passive"))
    )
    (net (code "79") (name "Vin") (class "Default")
      (node (ref "C1") (pin "1") (pinfunction "1_1") (pintype "passive"))
      (node (ref "C12") (pin "1") (pinfunction "1_1") (pintype "passive"))
      (node (ref "C3") (pin "1") (pinfunction "1_1") (pintype "passive"))
      (node (ref "D3") (pin "1") (pinfunction "RA_1") (pintype "passive"))
      (node (ref "D3") (pin "3") (pinfunction "GA_3") (pintype "passive"))
      (node (ref "D3") (pin "5") (pinfunction "BA_5") (pintype "passive"))
      (node (ref "D3") (pin "7") (pinfunction "WA_7") (pintype "passive"))
      (node (ref "D4") (pin "1") (pinfunction "RA_1") (pintype "passive"))
      (node (ref "D4") (pin "3") (pinfunction "GA_3") (pintype "passive"))
      (node (ref "D4") (pin "5") (pinfunction "BA_5") (pintype "passive"))
      (node (ref "D4") (pin "7") (pinfunction "WA_7") (pintype "passive"))
      (node (ref "D5") (pin "1") (pinfunction "RA_1") (pintype "passive"))
      (node (ref "D5") (pin "3") (pinfunction "GA_3") (pintype "passive"))
      (node (ref "D5") (pin "5") (pinfunction "BA_5") (pintype "passive"))
      (node (ref "D5") (pin "7") (pinfunction "WA_7") (pintype "passive"))
      (node (ref "F1") (pin "1") (pinfunction "1_1") (pintype "passive"))
      (node (ref "J1") (pin "1") (pinfunction "1_1") (pintype "passive"))
      (node (ref "P2") (pin "1") (pinfunction "1_1") (pintype "passive"))
      (node (ref "P2") (pin "4") (pinfunction "4_4") (pintype "passive"))
      (node (ref "U1") (pin "2") (pinfunction "VIN_2") (pintype "power_in"))
      (node (ref "U1") (pin "3") (pinfunction "EN_3") (pintype "input"))
      (node (ref "U2") (pin "3") (pinfunction "IN_3") (pintype "passive"))
    )
    (net (code "80") (name "unconnected-(P1-Pad2)") (class "Default")
      (node (ref "P1") (pin "2") (pinfunction "2_2") (pintype "passive+no_connect"))
    )
    (net (code "81") (name "unconnected-(P1-Pad3)") (class "Default")
      (node (ref "P1") (pin "3") (pinfunction "3_3") (pintype "passive+no_connect"))
    )
    (net (code "82") (name "unconnected-(U4-ALERT-Pad3)") (class "Default")
      (node (ref "U4") (pin "3") (pinfunction "ALERT_3") (pintype "output+no_connect"))
    )
    (net (code "83") (name "unconnected-(U5-N.C.-Pad2)") (class "Default")
      (node (ref "U5") (pin "2") (pinfunction "N.C._2") (pintype "passive+no_connect"))
    )
    (net (code "84") (name "unconnected-(U5-N.C.-Pad3)") (class "Default")
      (node (ref "U5") (pin "3") (pinfunction "N.C._3") (pintype "passive+no_connect"))
    )
    (net (code "85") (name "unconnected-(U5-N.C.-Pad5)") (class "Default")
      (node (ref "U5") (pin "5") (pinfunction "N.C._5") (pintype "passive+no_connect"))
    )
    (net (code "86") (name "unconnected-(U5-N.C.-Pad6)") (class "Default")
      (node (ref "U5") (pin "6") (pinfunction "N.C._6") (pintype "passive+no_connect"))
    )
    (net (code "87") (name "unconnected-(U5-N.C.-Pad7)") (class "Default")
      (node (ref "U5") (pin "7") (pinfunction "N.C._7") (pintype "passive+no_connect"))
    )
  )
)
